# orb-4.net
KiCad netlist of a schematic drawn in EAGLE
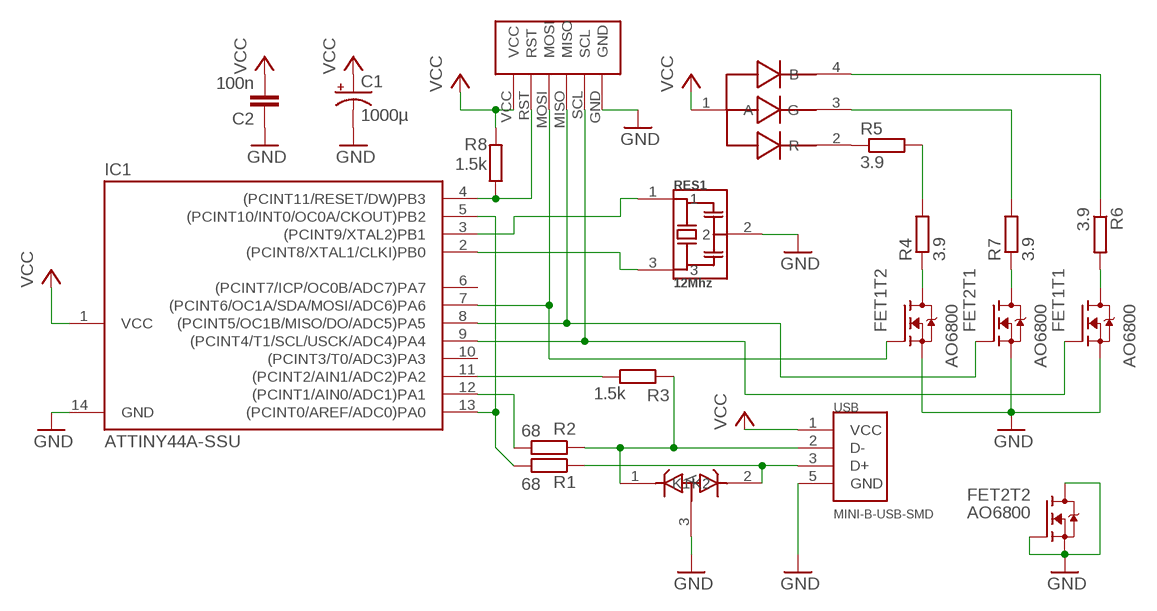
[diagram p0: schematic, sheet 1]

(export (version "E")
  (design (tool "Eeschema 10.0.6"))
  (components
    (comp (ref "C1")
      (value "1000µ")
      (footprint "eagle-import:PANASONIC_F")
      (libsource (lib "eagle-import") (part "CPOL-USF"))
    )
    (comp (ref "C2")
      (value "100n")
      (footprint "eagle-import:C0805K")
      (libsource (lib "eagle-import") (part "C-EUC0805K"))
    )
    (comp (ref "D1")
      (value "3.6V")
      (footprint "eagle-import:SOT23")
      (libsource (lib "eagle-import") (part "SOT23-DUAL-ZENER"))
    )
    (comp (ref "FET1")
      (value "AO6800")
      (footprint "eagle-import:TSOP6")
      (libsource (lib "eagle-import") (part "AO6800"))
    )
    (comp (ref "FET2")
      (value "AO6800")
      (footprint "eagle-import:TSOP6")
      (libsource (lib "eagle-import") (part "AO6800"))
    )
    (comp (ref "IC1")
      (value "ATTINY44A-SSU")
      (footprint "eagle-import:SOIC14")
      (libsource (lib "eagle-import") (part "ATTINY24/44/84-SSU"))
    )
    (comp (ref "R1")
      (value "68")
      (footprint "eagle-import:M0805")
      (libsource (lib "eagle-import") (part "R-EU_M0805"))
    )
    (comp (ref "R2")
      (value "68")
      (footprint "eagle-import:M0805")
      (libsource (lib "eagle-import") (part "R-EU_M0805"))
    )
    (comp (ref "R3")
      (value "1.5k")
      (footprint "eagle-import:M0805")
      (libsource (lib "eagle-import") (part "R-EU_M0805"))
    )
    (comp (ref "R4")
      (value "3.9")
      (footprint "eagle-import:R2512")
      (libsource (lib "eagle-import") (part "R-EU_R2512"))
    )
    (comp (ref "R5")
      (value "3.9")
      (footprint "eagle-import:R2512")
      (libsource (lib "eagle-import") (part "R-EU_R2512"))
    )
    (comp (ref "R6")
      (value "3.9")
      (footprint "eagle-import:R2512")
      (libsource (lib "eagle-import") (part "R-EU_R2512"))
    )
    (comp (ref "R7")
      (value "3.9")
      (footprint "eagle-import:R2512")
      (libsource (lib "eagle-import") (part "R-EU_R2512"))
    )
    (comp (ref "R8")
      (value "1.5k")
      (footprint "eagle-import:M0805")
      (libsource (lib "eagle-import") (part "R-EU_M0805"))
    )
    (comp (ref "RES1")
      (value "12Mhz")
      (footprint "eagle-import:AWSCR-CV")
      (libsource (lib "eagle-import") (part "RESONATOR"))
    )
    (comp (ref "U$1")
      (value "5W-RGB")
      (footprint "eagle-import:5W-POWER-LED")
      (libsource (lib "eagle-import") (part "5W-RGB"))
    )
    (comp (ref "U$2")
      (value "PROG-HEADER")
      (footprint "eagle-import:SMALL-PROG-HEADER")
      (libsource (lib "eagle-import") (part "PROG-HEADER"))
    )
    (comp (ref "USB")
      (value "MINI-B-USB-SMD")
      (footprint "eagle-import:USB-UX60SC-SMD")
      (libsource (lib "eagle-import") (part "MINI-B-USB-SMD"))
    )
  )
  (nets
    (net (code "1") (name "GND") (class "Default")
      (node (ref "C1") (pin "-") (pinfunction "-_-") (pintype "passive"))
      (node (ref "C2") (pin "1") (pinfunction "1_1") (pintype "passive"))
      (node (ref "D1") (pin "3") (pinfunction "A_3") (pintype "bidirectional"))
      (node (ref "FET1") (pin "2") (pinfunction "S_2") (pintype "passive"))
      (node (ref "FET1") (pin "5") (pinfunction "S_5") (pintype "passive"))
      (node (ref "FET2") (pin "2") (pinfunction "S_2") (pintype "passive"))
      (node (ref "FET2") (pin "3") (pinfunction "G_3") (pintype "passive"))
      (node (ref "FET2") (pin "4") (pinfunction "D_4") (pintype "passive"))
      (node (ref "FET2") (pin "5") (pinfunction "S_5") (pintype "passive"))
      (node (ref "IC1") (pin "14") (pinfunction "GND_14") (pintype "power_in"))
      (node (ref "RES1") (pin "2") (pinfunction "2_2") (pintype "bidirectional"))
      (node (ref "U$2") (pin "GND") (pinfunction "GND_GND") (pintype "bidirectional"))
      (node (ref "USB") (pin "5") (pinfunction "GND_5") (pintype "power_in"))
    )
    (net (code "2") (name "Net-(D1-K1)") (class "Default")
      (node (ref "D1") (pin "1") (pinfunction "K1_1") (pintype "bidirectional"))
      (node (ref "R2") (pin "1") (pinfunction "1_1") (pintype "passive"))
      (node (ref "R3") (pin "2") (pinfunction "2_2") (pintype "passive"))
      (node (ref "USB") (pin "2") (pinfunction "D-_2") (pintype "bidirectional"))
    )
    (net (code "3") (name "Net-(D1-K2)") (class "Default")
      (node (ref "D1") (pin "2") (pinfunction "K2_2") (pintype "bidirectional"))
      (node (ref "R1") (pin "1") (pinfunction "1_1") (pintype "passive"))
      (node (ref "USB") (pin "3") (pinfunction "D+_3") (pintype "bidirectional"))
    )
    (net (code "4") (name "Net-(FET1A-D)") (class "Default")
      (node (ref "FET1") (pin "6") (pinfunction "D_6") (pintype "passive"))
      (node (ref "R6") (pin "2") (pinfunction "2_2") (pintype "passive"))
    )
    (net (code "5") (name "Net-(FET1A-G)") (class "Default")
      (node (ref "FET1") (pin "1") (pinfunction "G_1") (pintype "passive"))
      (node (ref "IC1") (pin "9") (pinfunction "(PCINT4/T1/SCL/USCK/ADC4)PA4_9") (pintype "bidirectional"))
      (node (ref "U$2") (pin "SCL") (pinfunction "SCL_SCL") (pintype "bidirectional"))
    )
    (net (code "6") (name "Net-(FET1B-D)") (class "Default")
      (node (ref "FET1") (pin "4") (pinfunction "D_4") (pintype "passive"))
      (node (ref "R4") (pin "1") (pinfunction "1_1") (pintype "passive"))
    )
    (net (code "7") (name "Net-(FET1B-G)") (class "Default")
      (node (ref "FET1") (pin "3") (pinfunction "G_3") (pintype "passive"))
      (node (ref "IC1") (pin "7") (pinfunction "(PCINT6/OC1A/SDA/MOSI/ADC6)PA6_7") (pintype "bidirectional"))
      (node (ref "U$2") (pin "MOSI") (pinfunction "MOSI_MOSI") (pintype "bidirectional"))
    )
    (net (code "8") (name "Net-(FET2A-D)") (class "Default")
      (node (ref "FET2") (pin "6") (pinfunction "D_6") (pintype "passive"))
      (node (ref "R7") (pin "1") (pinfunction "1_1") (pintype "passive"))
    )
    (net (code "9") (name "Net-(FET2A-G)") (class "Default")
      (node (ref "FET2") (pin "1") (pinfunction "G_1") (pintype "passive"))
      (node (ref "IC1") (pin "8") (pinfunction "(PCINT5/OC1B/MISO/DO/ADC5)PA5_8") (pintype "bidirectional"))
      (node (ref "U$2") (pin "MISO") (pinfunction "MISO_MISO") (pintype "bidirectional"))
    )
    (net (code "10") (name "Net-(IC1-(PCINT0{slash}AREF{slash}ADC0)PA0)") (class "Default")
      (node (ref "IC1") (pin "13") (pinfunction "(PCINT0/AREF/ADC0)PA0_13") (pintype "bidirectional"))
      (node (ref "IC1") (pin "5") (pinfunction "(PCINT10/INT0/OC0A/CKOUT)PB2_5") (pintype "bidirectional"))
      (node (ref "R1") (pin "2") (pinfunction "2_2") (pintype "passive"))
    )
    (net (code "11") (name "Net-(IC1-(PCINT1{slash}AIN0{slash}ADC1)PA1)") (class "Default")
      (node (ref "IC1") (pin "12") (pinfunction "(PCINT1/AIN0/ADC1)PA1_12") (pintype "bidirectional"))
      (node (ref "R2") (pin "2") (pinfunction "2_2") (pintype "passive"))
    )
    (net (code "12") (name "Net-(IC1-(PCINT2{slash}AIN1{slash}ADC2)PA2)") (class "Default")
      (node (ref "IC1") (pin "11") (pinfunction "(PCINT2/AIN1/ADC2)PA2_11") (pintype "bidirectional"))
      (node (ref "R3") (pin "1") (pinfunction "1_1") (pintype "passive"))
    )
    (net (code "13") (name "Net-(IC1-(PCINT8{slash}XTAL1{slash}CLKI)PB0)") (class "Default")
      (node (ref "IC1") (pin "2") (pinfunction "(PCINT8/XTAL1/CLKI)PB0_2") (pintype "bidirectional"))
      (node (ref "RES1") (pin "3") (pinfunction "3_3") (pintype "bidirectional"))
    )
    (net (code "14") (name "Net-(IC1-(PCINT9{slash}XTAL2)PB1)") (class "Default")
      (node (ref "IC1") (pin "3") (pinfunction "(PCINT9/XTAL2)PB1_3") (pintype "bidirectional"))
      (node (ref "RES1") (pin "1") (pinfunction "1_1") (pintype "bidirectional"))
    )
    (net (code "15") (name "Net-(IC1-(PCINT11{slash}RESET{slash}DW)PB3)") (class "Default")
      (node (ref "IC1") (pin "4") (pinfunction "(PCINT11/RESET/DW)PB3_4") (pintype "bidirectional"))
      (node (ref "R8") (pin "1") (pinfunction "1_1") (pintype "passive"))
      (node (ref "U$2") (pin "RST") (pinfunction "RST_RST") (pintype "bidirectional"))
    )
    (net (code "16") (name "Net-(R4-Pad2)") (class "Default")
      (node (ref "R4") (pin "2") (pinfunction "2_2") (pintype "passive"))
      (node (ref "R5") (pin "2") (pinfunction "2_2") (pintype "passive"))
    )
    (net (code "17") (name "Net-(U$1-B)") (class "Default")
      (node (ref "R6") (pin "1") (pinfunction "1_1") (pintype "passive"))
      (node (ref "U$1") (pin "4") (pinfunction "B_4") (pintype "bidirectional"))
    )
    (net (code "18") (name "Net-(U$1-G)") (class "Default")
      (node (ref "R7") (pin "2") (pinfunction "2_2") (pintype "passive"))
      (node (ref "U$1") (pin "3") (pinfunction "G_3") (pintype "bidirectional"))
    )
    (net (code "19") (name "Net-(U$1-R)") (class "Default")
      (node (ref "R5") (pin "1") (pinfunction "1_1") (pintype "passive"))
      (node (ref "U$1") (pin "2") (pinfunction "R_2") (pintype "bidirectional"))
    )
    (net (code "20") (name "VCC") (class "Default")
      (node (ref "C1") (pin "+") (pinfunction "+_+") (pintype "passive"))
      (node (ref "C2") (pin "2") (pinfunction "2_2") (pintype "passive"))
      (node (ref "IC1") (pin "1") (pinfunction "VCC_1") (pintype "power_in"))
      (node (ref "R8") (pin "2") (pinfunction "2_2") (pintype "passive"))
      (node (ref "U$1") (pin "1") (pinfunction "A_1") (pintype "bidirectional"))
      (node (ref "U$2") (pin "VCC") (pinfunction "VCC_VCC") (pintype "bidirectional"))
      (node (ref "USB") (pin "1") (pinfunction "VCC_1") (pintype "power_in"))
    )
    (net (code "21") (name "unconnected-(IC1-(PCINT3{slash}T0{slash}ADC3)PA3-Pad10)") (class "Default")
      (node (ref "IC1") (pin "10") (pinfunction "(PCINT3/T0/ADC3)PA3_10") (pintype "bidirectional"))
    )
    (net (code "22") (name "unconnected-(IC1-(PCINT7{slash}ICP{slash}OC0B{slash}ADC7)PA7-Pad6)") (class "Default")
      (node (ref "IC1") (pin "6") (pinfunction "(PCINT7/ICP/OC0B/ADC7)PA7_6") (pintype "bidirectional"))
    )
  )
)
